# s2.net
KiCad netlist of a schematic drawn in EAGLE
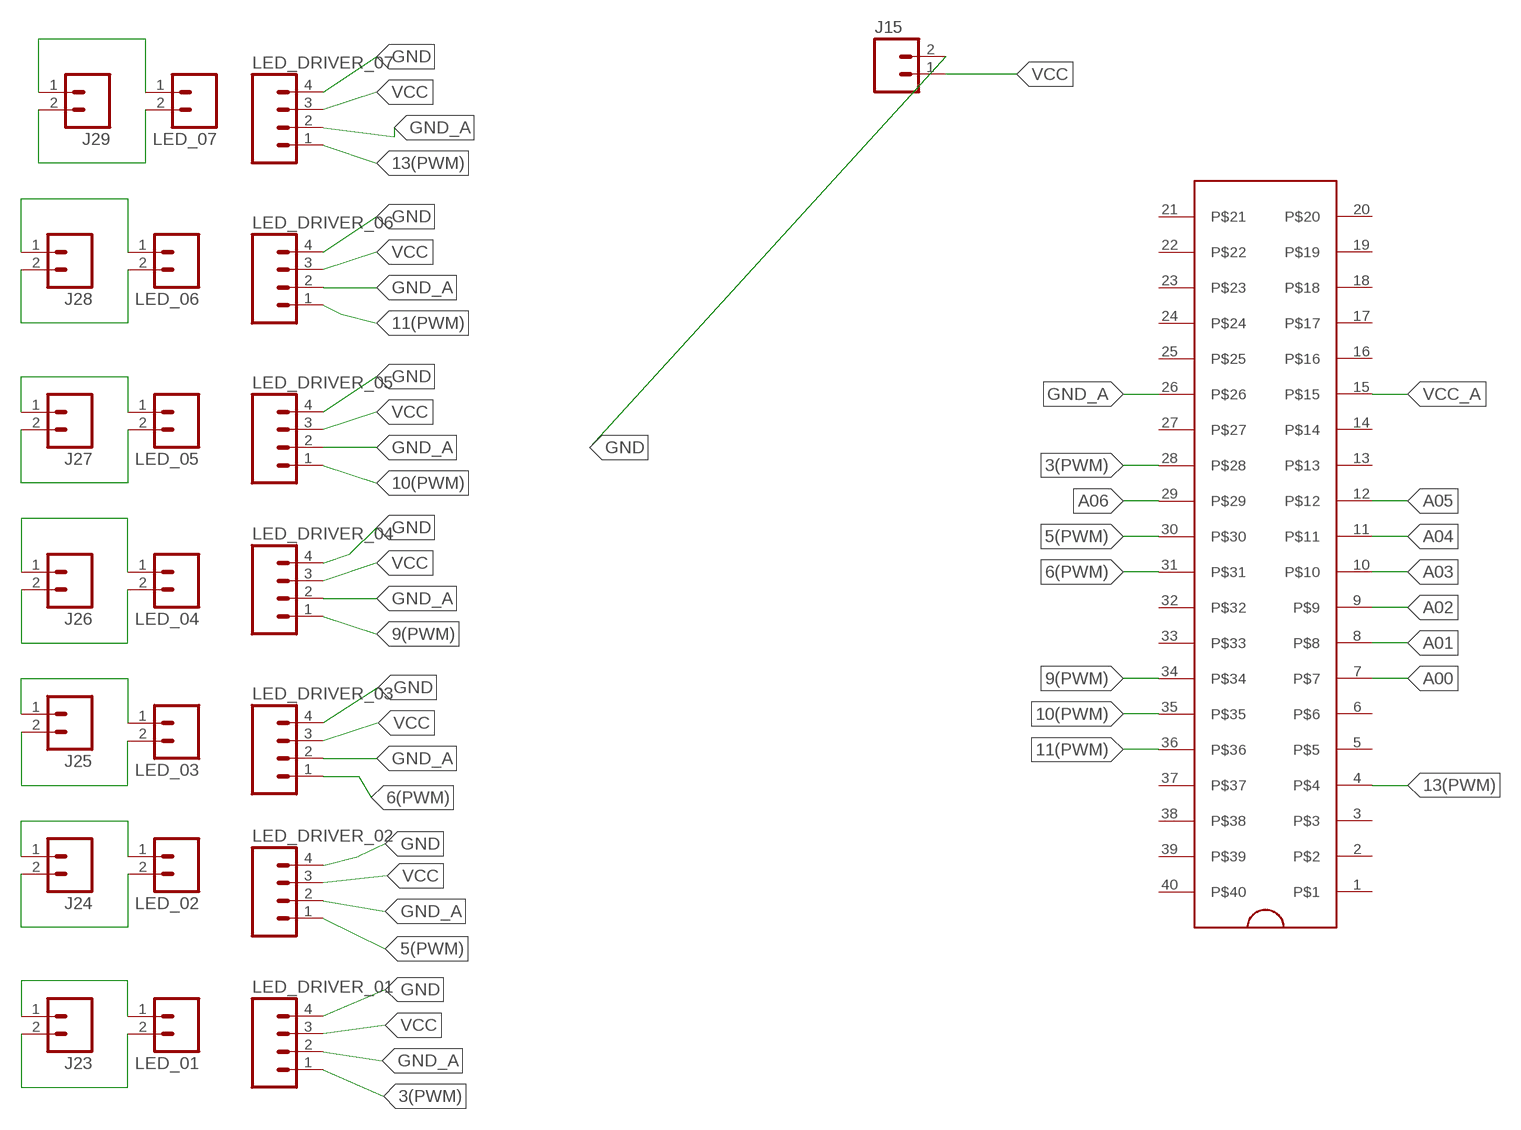
[diagram p0: schematic, sheet 1]

(export (version "E")
  (design (tool "Eeschema 10.0.6"))
  (components
    (comp (ref "ARDUINO_MICRO")
      (value "ZIFSOCKET-40-6DIL40-6-ZIF_SOCKET")
      (footprint "eagle-import:DIL40-6-ZIF_SOCKET")
      (libsource (lib "eagle-import") (part "ZIFSOCKET-40-6DIL40-6-ZIF_SOCKET"))
    )
    (comp (ref "J15")
      (value "M02PTH")
      (footprint "eagle-import:1X02")
      (libsource (lib "eagle-import") (part "M02PTH"))
    )
    (comp (ref "J23")
      (value "M02PTH")
      (footprint "eagle-import:1X02")
      (libsource (lib "eagle-import") (part "M02PTH"))
    )
    (comp (ref "J24")
      (value "M02PTH")
      (footprint "eagle-import:1X02")
      (libsource (lib "eagle-import") (part "M02PTH"))
    )
    (comp (ref "J25")
      (value "M02PTH")
      (footprint "eagle-import:1X02")
      (libsource (lib "eagle-import") (part "M02PTH"))
    )
    (comp (ref "J26")
      (value "M02PTH")
      (footprint "eagle-import:1X02")
      (libsource (lib "eagle-import") (part "M02PTH"))
    )
    (comp (ref "J27")
      (value "M02PTH")
      (footprint "eagle-import:1X02")
      (libsource (lib "eagle-import") (part "M02PTH"))
    )
    (comp (ref "J28")
      (value "M02PTH")
      (footprint "eagle-import:1X02")
      (libsource (lib "eagle-import") (part "M02PTH"))
    )
    (comp (ref "J29")
      (value "M02PTH")
      (footprint "eagle-import:1X02")
      (libsource (lib "eagle-import") (part "M02PTH"))
    )
    (comp (ref "LED_01")
      (value "M02PTH")
      (footprint "eagle-import:1X02")
      (libsource (lib "eagle-import") (part "M02PTH"))
    )
    (comp (ref "LED_02")
      (value "M02PTH")
      (footprint "eagle-import:1X02")
      (libsource (lib "eagle-import") (part "M02PTH"))
    )
    (comp (ref "LED_03")
      (value "M02PTH")
      (footprint "eagle-import:1X02")
      (libsource (lib "eagle-import") (part "M02PTH"))
    )
    (comp (ref "LED_04")
      (value "M02PTH")
      (footprint "eagle-import:1X02")
      (libsource (lib "eagle-import") (part "M02PTH"))
    )
    (comp (ref "LED_05")
      (value "M02PTH")
      (footprint "eagle-import:1X02")
      (libsource (lib "eagle-import") (part "M02PTH"))
    )
    (comp (ref "LED_06")
      (value "M02PTH")
      (footprint "eagle-import:1X02")
      (libsource (lib "eagle-import") (part "M02PTH"))
    )
    (comp (ref "LED_07")
      (value "M02PTH")
      (footprint "eagle-import:1X02")
      (libsource (lib "eagle-import") (part "M02PTH"))
    )
    (comp (ref "LED_DRIVER_01")
      (value "M04PTH")
      (footprint "eagle-import:1X04")
      (libsource (lib "eagle-import") (part "M04PTH"))
    )
    (comp (ref "LED_DRIVER_02")
      (value "M04PTH")
      (footprint "eagle-import:1X04")
      (libsource (lib "eagle-import") (part "M04PTH"))
    )
    (comp (ref "LED_DRIVER_03")
      (value "M04PTH")
      (footprint "eagle-import:1X04")
      (libsource (lib "eagle-import") (part "M04PTH"))
    )
    (comp (ref "LED_DRIVER_04")
      (value "M04PTH")
      (footprint "eagle-import:1X04")
      (libsource (lib "eagle-import") (part "M04PTH"))
    )
    (comp (ref "LED_DRIVER_05")
      (value "M04PTH")
      (footprint "eagle-import:1X04")
      (libsource (lib "eagle-import") (part "M04PTH"))
    )
    (comp (ref "LED_DRIVER_06")
      (value "M04PTH")
      (footprint "eagle-import:1X04")
      (libsource (lib "eagle-import") (part "M04PTH"))
    )
    (comp (ref "LED_DRIVER_07")
      (value "M04PTH")
      (footprint "eagle-import:1X04")
      (libsource (lib "eagle-import") (part "M04PTH"))
    )
  )
  (nets
    (net (code "1") (name "3(PWM)") (class "Default")
      (node (ref "ARDUINO_MICRO") (pin "28") (pinfunction "P$28_28") (pintype "bidirectional"))
      (node (ref "LED_DRIVER_01") (pin "1") (pinfunction "1_1") (pintype "passive"))
    )
    (net (code "2") (name "5(PWM)") (class "Default")
      (node (ref "ARDUINO_MICRO") (pin "30") (pinfunction "P$30_30") (pintype "bidirectional"))
      (node (ref "LED_DRIVER_02") (pin "1") (pinfunction "1_1") (pintype "passive"))
    )
    (net (code "3") (name "6(PWM)") (class "Default")
      (node (ref "ARDUINO_MICRO") (pin "31") (pinfunction "P$31_31") (pintype "bidirectional"))
      (node (ref "LED_DRIVER_03") (pin "1") (pinfunction "1_1") (pintype "passive"))
    )
    (net (code "4") (name "9(PWM)") (class "Default")
      (node (ref "ARDUINO_MICRO") (pin "34") (pinfunction "P$34_34") (pintype "bidirectional"))
      (node (ref "LED_DRIVER_04") (pin "1") (pinfunction "1_1") (pintype "passive"))
    )
    (net (code "5") (name "10(PWM)") (class "Default")
      (node (ref "ARDUINO_MICRO") (pin "35") (pinfunction "P$35_35") (pintype "bidirectional"))
      (node (ref "LED_DRIVER_05") (pin "1") (pinfunction "1_1") (pintype "passive"))
    )
    (net (code "6") (name "11(PWM)") (class "Default")
      (node (ref "ARDUINO_MICRO") (pin "36") (pinfunction "P$36_36") (pintype "bidirectional"))
      (node (ref "LED_DRIVER_06") (pin "1") (pinfunction "1_1") (pintype "passive"))
    )
    (net (code "7") (name "13(PWM)") (class "Default")
      (node (ref "ARDUINO_MICRO") (pin "4") (pinfunction "P$4_4") (pintype "bidirectional"))
      (node (ref "LED_DRIVER_07") (pin "1") (pinfunction "1_1") (pintype "passive"))
    )
    (net (code "8") (name "A00") (class "Default")
      (node (ref "ARDUINO_MICRO") (pin "7") (pinfunction "P$7_7") (pintype "bidirectional"))
    )
    (net (code "9") (name "A01") (class "Default")
      (node (ref "ARDUINO_MICRO") (pin "8") (pinfunction "P$8_8") (pintype "bidirectional"))
    )
    (net (code "10") (name "A02") (class "Default")
      (node (ref "ARDUINO_MICRO") (pin "9") (pinfunction "P$9_9") (pintype "bidirectional"))
    )
    (net (code "11") (name "A03") (class "Default")
      (node (ref "ARDUINO_MICRO") (pin "10") (pinfunction "P$10_10") (pintype "bidirectional"))
    )
    (net (code "12") (name "A04") (class "Default")
      (node (ref "ARDUINO_MICRO") (pin "11") (pinfunction "P$11_11") (pintype "bidirectional"))
    )
    (net (code "13") (name "A05") (class "Default")
      (node (ref "ARDUINO_MICRO") (pin "12") (pinfunction "P$12_12") (pintype "bidirectional"))
    )
    (net (code "14") (name "A06") (class "Default")
      (node (ref "ARDUINO_MICRO") (pin "29") (pinfunction "P$29_29") (pintype "bidirectional"))
    )
    (net (code "15") (name "GND") (class "Default")
      (node (ref "J15") (pin "2") (pinfunction "2_2") (pintype "passive"))
      (node (ref "LED_DRIVER_01") (pin "4") (pinfunction "4_4") (pintype "passive"))
      (node (ref "LED_DRIVER_02") (pin "4") (pinfunction "4_4") (pintype "passive"))
      (node (ref "LED_DRIVER_03") (pin "4") (pinfunction "4_4") (pintype "passive"))
      (node (ref "LED_DRIVER_04") (pin "4") (pinfunction "4_4") (pintype "passive"))
      (node (ref "LED_DRIVER_05") (pin "4") (pinfunction "4_4") (pintype "passive"))
      (node (ref "LED_DRIVER_06") (pin "4") (pinfunction "4_4") (pintype "passive"))
      (node (ref "LED_DRIVER_07") (pin "4") (pinfunction "4_4") (pintype "passive"))
    )
    (net (code "16") (name "GND_A") (class "Default")
      (node (ref "ARDUINO_MICRO") (pin "26") (pinfunction "P$26_26") (pintype "bidirectional"))
      (node (ref "LED_DRIVER_01") (pin "2") (pinfunction "2_2") (pintype "passive"))
      (node (ref "LED_DRIVER_02") (pin "2") (pinfunction "2_2") (pintype "passive"))
      (node (ref "LED_DRIVER_03") (pin "2") (pinfunction "2_2") (pintype "passive"))
      (node (ref "LED_DRIVER_04") (pin "2") (pinfunction "2_2") (pintype "passive"))
      (node (ref "LED_DRIVER_05") (pin "2") (pinfunction "2_2") (pintype "passive"))
      (node (ref "LED_DRIVER_06") (pin "2") (pinfunction "2_2") (pintype "passive"))
      (node (ref "LED_DRIVER_07") (pin "2") (pinfunction "2_2") (pintype "passive"))
    )
    (net (code "17") (name "Net-(J23-Pad1)") (class "Default")
      (node (ref "J23") (pin "1") (pinfunction "1_1") (pintype "passive"))
      (node (ref "LED_01") (pin "1") (pinfunction "1_1") (pintype "passive"))
    )
    (net (code "18") (name "Net-(J23-Pad2)") (class "Default")
      (node (ref "J23") (pin "2") (pinfunction "2_2") (pintype "passive"))
      (node (ref "LED_01") (pin "2") (pinfunction "2_2") (pintype "passive"))
    )
    (net (code "19") (name "Net-(J24-Pad1)") (class "Default")
      (node (ref "J24") (pin "1") (pinfunction "1_1") (pintype "passive"))
      (node (ref "LED_02") (pin "1") (pinfunction "1_1") (pintype "passive"))
    )
    (net (code "20") (name "Net-(J24-Pad2)") (class "Default")
      (node (ref "J24") (pin "2") (pinfunction "2_2") (pintype "passive"))
      (node (ref "LED_02") (pin "2") (pinfunction "2_2") (pintype "passive"))
    )
    (net (code "21") (name "Net-(J25-Pad1)") (class "Default")
      (node (ref "J25") (pin "1") (pinfunction "1_1") (pintype "passive"))
      (node (ref "LED_03") (pin "1") (pinfunction "1_1") (pintype "passive"))
    )
    (net (code "22") (name "Net-(J25-Pad2)") (class "Default")
      (node (ref "J25") (pin "2") (pinfunction "2_2") (pintype "passive"))
      (node (ref "LED_03") (pin "2") (pinfunction "2_2") (pintype "passive"))
    )
    (net (code "23") (name "Net-(J26-Pad1)") (class "Default")
      (node (ref "J26") (pin "1") (pinfunction "1_1") (pintype "passive"))
      (node (ref "LED_04") (pin "1") (pinfunction "1_1") (pintype "passive"))
    )
    (net (code "24") (name "Net-(J26-Pad2)") (class "Default")
      (node (ref "J26") (pin "2") (pinfunction "2_2") (pintype "passive"))
      (node (ref "LED_04") (pin "2") (pinfunction "2_2") (pintype "passive"))
    )
    (net (code "25") (name "Net-(J27-Pad1)") (class "Default")
      (node (ref "J27") (pin "1") (pinfunction "1_1") (pintype "passive"))
      (node (ref "LED_05") (pin "1") (pinfunction "1_1") (pintype "passive"))
    )
    (net (code "26") (name "Net-(J27-Pad2)") (class "Default")
      (node (ref "J27") (pin "2") (pinfunction "2_2") (pintype "passive"))
      (node (ref "LED_05") (pin "2") (pinfunction "2_2") (pintype "passive"))
    )
    (net (code "27") (name "Net-(J28-Pad1)") (class "Default")
      (node (ref "J28") (pin "1") (pinfunction "1_1") (pintype "passive"))
      (node (ref "LED_06") (pin "1") (pinfunction "1_1") (pintype "passive"))
    )
    (net (code "28") (name "Net-(J28-Pad2)") (class "Default")
      (node (ref "J28") (pin "2") (pinfunction "2_2") (pintype "passive"))
      (node (ref "LED_06") (pin "2") (pinfunction "2_2") (pintype "passive"))
    )
    (net (code "29") (name "Net-(J29-Pad1)") (class "Default")
      (node (ref "J29") (pin "1") (pinfunction "1_1") (pintype "passive"))
      (node (ref "LED_07") (pin "1") (pinfunction "1_1") (pintype "passive"))
    )
    (net (code "30") (name "Net-(J29-Pad2)") (class "Default")
      (node (ref "J29") (pin "2") (pinfunction "2_2") (pintype "passive"))
      (node (ref "LED_07") (pin "2") (pinfunction "2_2") (pintype "passive"))
    )
    (net (code "31") (name "VCC") (class "Default")
      (node (ref "J15") (pin "1") (pinfunction "1_1") (pintype "passive"))
      (node (ref "LED_DRIVER_01") (pin "3") (pinfunction "3_3") (pintype "passive"))
      (node (ref "LED_DRIVER_02") (pin "3") (pinfunction "3_3") (pintype "passive"))
      (node (ref "LED_DRIVER_03") (pin "3") (pinfunction "3_3") (pintype "passive"))
      (node (ref "LED_DRIVER_04") (pin "3") (pinfunction "3_3") (pintype "passive"))
      (node (ref "LED_DRIVER_05") (pin "3") (pinfunction "3_3") (pintype "passive"))
      (node (ref "LED_DRIVER_06") (pin "3") (pinfunction "3_3") (pintype "passive"))
      (node (ref "LED_DRIVER_07") (pin "3") (pinfunction "3_3") (pintype "passive"))
    )
    (net (code "32") (name "VCC_A") (class "Default")
      (node (ref "ARDUINO_MICRO") (pin "15") (pinfunction "P$15_15") (pintype "bidirectional"))
    )
    (net (code "33") (name "unconnected-(ARDUINO_MICRO-P$1-Pad1)") (class "Default")
      (node (ref "ARDUINO_MICRO") (pin "1") (pinfunction "P$1_1") (pintype "bidirectional"))
    )
    (net (code "34") (name "unconnected-(ARDUINO_MICRO-P$2-Pad2)") (class "Default")
      (node (ref "ARDUINO_MICRO") (pin "2") (pinfunction "P$2_2") (pintype "bidirectional"))
    )
    (net (code "35") (name "unconnected-(ARDUINO_MICRO-P$3-Pad3)") (class "Default")
      (node (ref "ARDUINO_MICRO") (pin "3") (pinfunction "P$3_3") (pintype "bidirectional"))
    )
    (net (code "36") (name "unconnected-(ARDUINO_MICRO-P$5-Pad5)") (class "Default")
      (node (ref "ARDUINO_MICRO") (pin "5") (pinfunction "P$5_5") (pintype "bidirectional"))
    )
    (net (code "37") (name "unconnected-(ARDUINO_MICRO-P$6-Pad6)") (class "Default")
      (node (ref "ARDUINO_MICRO") (pin "6") (pinfunction "P$6_6") (pintype "bidirectional"))
    )
    (net (code "38") (name "unconnected-(ARDUINO_MICRO-P$13-Pad13)") (class "Default")
      (node (ref "ARDUINO_MICRO") (pin "13") (pinfunction "P$13_13") (pintype "bidirectional"))
    )
    (net (code "39") (name "unconnected-(ARDUINO_MICRO-P$14-Pad14)") (class "Default")
      (node (ref "ARDUINO_MICRO") (pin "14") (pinfunction "P$14_14") (pintype "bidirectional"))
    )
    (net (code "40") (name "unconnected-(ARDUINO_MICRO-P$16-Pad16)") (class "Default")
      (node (ref "ARDUINO_MICRO") (pin "16") (pinfunction "P$16_16") (pintype "bidirectional"))
    )
    (net (code "41") (name "unconnected-(ARDUINO_MICRO-P$17-Pad17)") (class "Default")
      (node (ref "ARDUINO_MICRO") (pin "17") (pinfunction "P$17_17") (pintype "bidirectional"))
    )
    (net (code "42") (name "unconnected-(ARDUINO_MICRO-P$18-Pad18)") (class "Default")
      (node (ref "ARDUINO_MICRO") (pin "18") (pinfunction "P$18_18") (pintype "bidirectional"))
    )
    (net (code "43") (name "unconnected-(ARDUINO_MICRO-P$19-Pad19)") (class "Default")
      (node (ref "ARDUINO_MICRO") (pin "19") (pinfunction "P$19_19") (pintype "bidirectional"))
    )
    (net (code "44") (name "unconnected-(ARDUINO_MICRO-P$20-Pad20)") (class "Default")
      (node (ref "ARDUINO_MICRO") (pin "20") (pinfunction "P$20_20") (pintype "bidirectional"))
    )
    (net (code "45") (name "unconnected-(ARDUINO_MICRO-P$21-Pad21)") (class "Default")
      (node (ref "ARDUINO_MICRO") (pin "21") (pinfunction "P$21_21") (pintype "bidirectional"))
    )
    (net (code "46") (name "unconnected-(ARDUINO_MICRO-P$22-Pad22)") (class "Default")
      (node (ref "ARDUINO_MICRO") (pin "22") (pinfunction "P$22_22") (pintype "bidirectional"))
    )
    (net (code "47") (name "unconnected-(ARDUINO_MICRO-P$23-Pad23)") (class "Default")
      (node (ref "ARDUINO_MICRO") (pin "23") (pinfunction "P$23_23") (pintype "bidirectional"))
    )
    (net (code "48") (name "unconnected-(ARDUINO_MICRO-P$24-Pad24)") (class "Default")
      (node (ref "ARDUINO_MICRO") (pin "24") (pinfunction "P$24_24") (pintype "bidirectional"))
    )
    (net (code "49") (name "unconnected-(ARDUINO_MICRO-P$25-Pad25)") (class "Default")
      (node (ref "ARDUINO_MICRO") (pin "25") (pinfunction "P$25_25") (pintype "bidirectional"))
    )
    (net (code "50") (name "unconnected-(ARDUINO_MICRO-P$27-Pad27)") (class "Default")
      (node (ref "ARDUINO_MICRO") (pin "27") (pinfunction "P$27_27") (pintype "bidirectional"))
    )
    (net (code "51") (name "unconnected-(ARDUINO_MICRO-P$32-Pad32)") (class "Default")
      (node (ref "ARDUINO_MICRO") (pin "32") (pinfunction "P$32_32") (pintype "bidirectional"))
    )
    (net (code "52") (name "unconnected-(ARDUINO_MICRO-P$33-Pad33)") (class "Default")
      (node (ref "ARDUINO_MICRO") (pin "33") (pinfunction "P$33_33") (pintype "bidirectional"))
    )
    (net (code "53") (name "unconnected-(ARDUINO_MICRO-P$37-Pad37)") (class "Default")
      (node (ref "ARDUINO_MICRO") (pin "37") (pinfunction "P$37_37") (pintype "bidirectional"))
    )
    (net (code "54") (name "unconnected-(ARDUINO_MICRO-P$38-Pad38)") (class "Default")
      (node (ref "ARDUINO_MICRO") (pin "38") (pinfunction "P$38_38") (pintype "bidirectional"))
    )
    (net (code "55") (name "unconnected-(ARDUINO_MICRO-P$39-Pad39)") (class "Default")
      (node (ref "ARDUINO_MICRO") (pin "39") (pinfunction "P$39_39") (pintype "bidirectional"))
    )
    (net (code "56") (name "unconnected-(ARDUINO_MICRO-P$40-Pad40)") (class "Default")
      (node (ref "ARDUINO_MICRO") (pin "40") (pinfunction "P$40_40") (pintype "bidirectional"))
    )
  )
)
